# E17-04-TSVP.net
KiCad netlist of a schematic drawn in Altium Designer
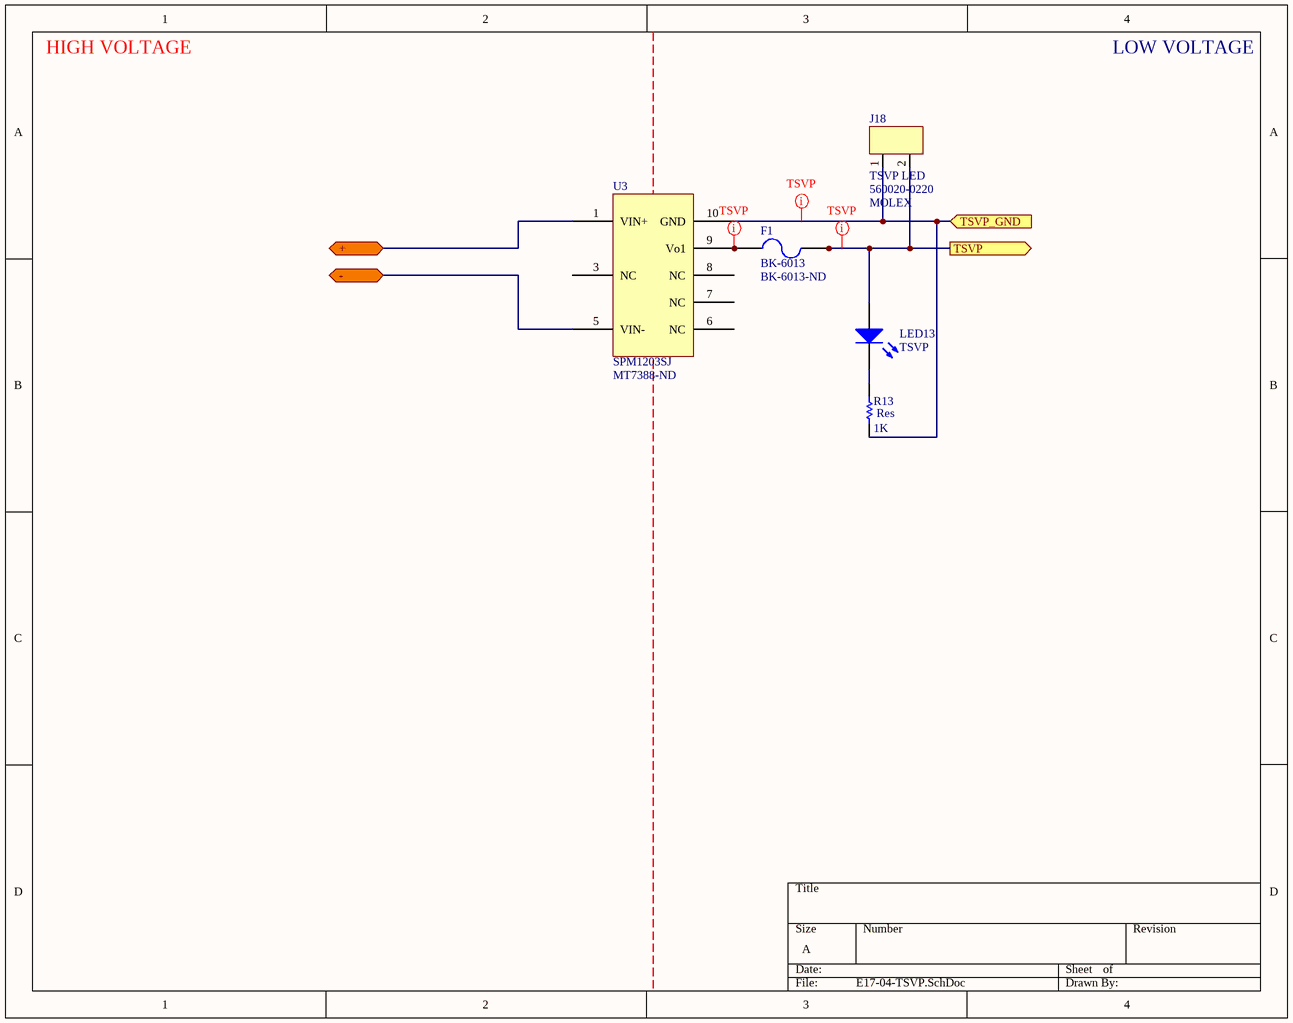
[diagram p0: E17-04-TSVP.SchDoc]

(export (version "E")
  (design (tool "Eeschema 10.0.6"))
  (components
    (comp (ref "F1")
      (value "BK-6013")
      (footprint "BK-6013")
      (description "FUSE HOLDER BLADE PCB")
      (fields (field (name "SUPPLIER PART NUMBER 1") "BK-6013-ND"))
      (libsource (lib "Fuses") (part "BK-6013"))
    )
    (comp (ref "J18")
      (value "TSVP LED")
      (footprint "MOLEX_DURACLIK_2 NAT VERT")
      (description "MOLEX DURACLIK 2-PIN VERT NAT")
      (fields
        (field (name "VOLTAGE") "125")
        (field (name "MPN") "560020-0220")
        (field (name "MANUFACTURER") "MOLEX")
      )
      (libsource (lib "Molex_DuraClik") (part "560020-0220"))
    )
    (comp (ref "LED13")
      (value "TSVP")
      (footprint "155124VS73200")
      (description "Right Angle SMD Green 2V")
      (fields
        (field (name "MANUFACTURER") "Wurth Electronics Inc")
        (field (name "MANUFACTURER PART NUMBER") "155124VS73200")
      )
      (libsource (lib "LEDs") (part "155124VS73200"))
    )
    (comp (ref "R13")
      (value "Res")
      (footprint "2012[0805]")
      (description "Surface Mount Resistor")
      (fields (field (name "ALTIUM_VALUE") "1K") (field (name "PUBLISHER") "Altium Limited"))
      (libsource (lib "Resistors") (part "Res"))
    )
    (comp (ref "U3")
      (value "SPM1203SJ")
      (footprint "SPM1203SJ")
      (fields (field (name "SUPPLIER PART NUMBER 1") "MT7388-ND"))
      (libsource (lib "Voltage Regulation") (part "SPM1203SJ"))
    )
  )
  (nets
    (net (code "1") (name "/+") (class "Default")
      (node (ref "U3") (pin "1") (pinfunction "VIN+_1") (pintype "passive"))
    )
    (net (code "2") (name "/-") (class "Default")
      (node (ref "U3") (pin "5") (pinfunction "VIN-_5") (pintype "passive"))
    )
    (net (code "3") (name "/TSVP") (class "Default")
      (node (ref "F1") (pin "3") (pinfunction "3_3") (pintype "passive"))
      (node (ref "F1") (pin "4") (pinfunction "4_4") (pintype "passive"))
      (node (ref "J18") (pin "2") (pinfunction "2_2") (pintype "passive"))
      (node (ref "LED13") (pin "2") (pinfunction "2_2") (pintype "passive"))
    )
    (net (code "4") (name "/TSVP_GND") (class "Default")
      (node (ref "J18") (pin "1") (pinfunction "1_1") (pintype "passive"))
      (node (ref "R13") (pin "1") (pinfunction "1_1") (pintype "passive"))
      (node (ref "U3") (pin "10") (pinfunction "GND_10") (pintype "passive"))
    )
    (net (code "5") (name "Net-(LED13-Pad1)") (class "Default")
      (node (ref "LED13") (pin "1") (pinfunction "1_1") (pintype "passive"))
      (node (ref "R13") (pin "2") (pinfunction "2_2") (pintype "passive"))
    )
    (net (code "6") (name "Net-(U3-Vo1)") (class "Default")
      (node (ref "F1") (pin "1") (pinfunction "1_1") (pintype "passive"))
      (node (ref "F1") (pin "2") (pinfunction "2_2") (pintype "passive"))
      (node (ref "U3") (pin "9") (pinfunction "Vo1_9") (pintype "passive"))
    )
    (net (code "7") (name "unconnected-(U3-NC-Pad3)") (class "Default")
      (node (ref "U3") (pin "3") (pinfunction "NC_3") (pintype "passive"))
    )
    (net (code "8") (name "unconnected-(U3-NC-Pad6)") (class "Default")
      (node (ref "U3") (pin "6") (pinfunction "NC_6") (pintype "passive"))
    )
    (net (code "9") (name "unconnected-(U3-NC-Pad7)") (class "Default")
      (node (ref "U3") (pin "7") (pinfunction "NC_7") (pintype "passive"))
    )
    (net (code "10") (name "unconnected-(U3-NC-Pad8)") (class "Default")
      (node (ref "U3") (pin "8") (pinfunction "NC_8") (pintype "passive"))
    )
  )
)
